# Sheet3.net
KiCad netlist of a schematic drawn in Altium Designer
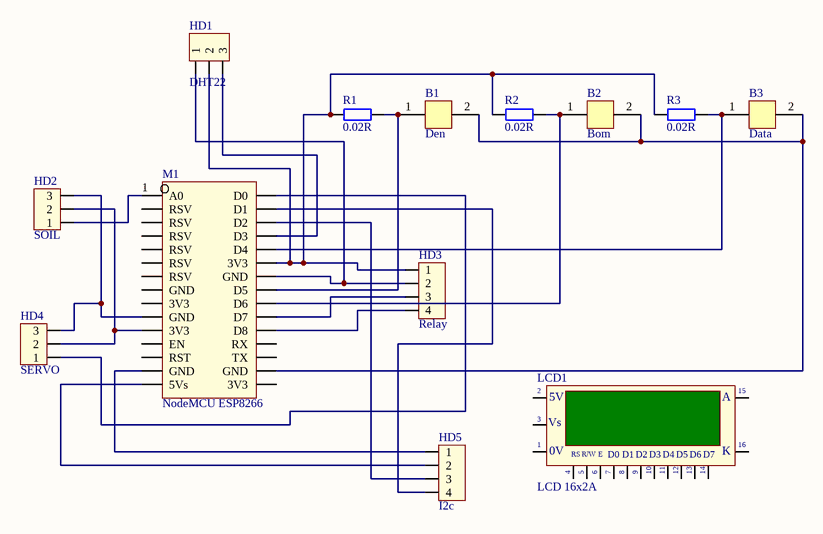
[diagram p0: Sheet3.SchDoc]

(export (version "E")
  (design (tool "Eeschema 10.0.6"))
  (components
    (comp (ref "B1")
      (value "Den")
      (footprint "Button 2 Pin")
      (description "Cắm")
      (libsource (lib "THU VIEN SCH") (part "Nut Nhan 2 Chan  6x6x5MM"))
    )
    (comp (ref "B2")
      (value "Bom")
      (footprint "Button 2 Pin")
      (description "Cắm")
      (libsource (lib "THU VIEN SCH") (part "Nut Nhan 2 Chan  6x6x5MM"))
    )
    (comp (ref "B3")
      (value "Data")
      (footprint "Button 2 Pin")
      (description "Cắm")
      (libsource (lib "THU VIEN SCH") (part "Nut Nhan 2 Chan  6x6x5MM"))
    )
    (comp (ref "HD1")
      (value "DHT22")
      (footprint "HED3")
      (description "Header 3 (Green)")
      (libsource (lib "") (part "Hed3_1"))
    )
    (comp (ref "HD2")
      (value "SOIL")
      (footprint "HED3")
      (description "Header 3 (Green)")
      (libsource (lib "syhaunguyen") (part "Hed3"))
    )
    (comp (ref "HD3")
      (value "Relay")
      (footprint "HED4")
      (description "Header 4 (Green)")
      (libsource (lib "syhaunguyen") (part "Hed4"))
    )
    (comp (ref "HD4")
      (value "SERVO")
      (footprint "HED3")
      (description "Header 3 (Green)")
      (libsource (lib "syhaunguyen") (part "Hed3"))
    )
    (comp (ref "HD5")
      (value "I2c")
      (footprint "HED4")
      (description "Header 4 (Green)")
      (libsource (lib "syhaunguyen") (part "Hed4"))
    )
    (comp (ref "LCD1")
      (value "LCD 16x2A")
      (footprint "LCD16X2")
      (description "LCD dipslay 16 char, 2 line")
      (libsource (lib "My Library") (part "LCD16x2A"))
    )
    (comp (ref "M1")
      (value "NodeMCU ESP8266")
      (footprint "NodeMCU ESP8266")
      (libsource (lib "NodeMCU ESP8266") (part "NodeMCU ESP8266"))
    )
    (comp (ref "R1")
      (value "0.02R")
      (footprint "tro vach 3w")
      (description "Cắm")
      (libsource (lib "THU VIEN SCH") (part "Tro Vach 3W 5% 0.02R"))
    )
    (comp (ref "R2")
      (value "0.02R")
      (footprint "tro vach 3w")
      (description "Cắm")
      (libsource (lib "THU VIEN SCH") (part "Tro Vach 3W 5% 0.02R"))
    )
    (comp (ref "R3")
      (value "0.02R")
      (footprint "tro vach 3w")
      (description "Cắm")
      (libsource (lib "THU VIEN SCH") (part "Tro Vach 3W 5% 0.02R"))
    )
  )
  (nets
    (net (code "1") (name "Net-(B1-Pad2)") (class "Default")
      (node (ref "B1") (pin "2") (pinfunction "2_2") (pintype "passive"))
      (node (ref "B2") (pin "2") (pinfunction "2_2") (pintype "passive"))
      (node (ref "B3") (pin "2") (pinfunction "2_2") (pintype "passive"))
      (node (ref "M1") (pin "17") (pinfunction "GND_17") (pintype "passive"))
    )
    (net (code "2") (name "Net-(HD1-Pad1)") (class "Default")
      (node (ref "HD1") (pin "1") (pinfunction "1_1") (pintype "passive"))
      (node (ref "HD3") (pin "2") (pinfunction "2_2") (pintype "passive"))
      (node (ref "M1") (pin "24") (pinfunction "GND_24") (pintype "passive"))
    )
    (net (code "3") (name "Net-(HD1-Pad2)") (class "Default")
      (node (ref "HD1") (pin "2") (pinfunction "2_2") (pintype "passive"))
      (node (ref "HD3") (pin "1") (pinfunction "1_1") (pintype "passive"))
      (node (ref "M1") (pin "25") (pinfunction "3V3_25") (pintype "passive"))
      (node (ref "R1") (pin "1") (pinfunction "1_1") (pintype "passive"))
      (node (ref "R2") (pin "1") (pinfunction "1_1") (pintype "passive"))
      (node (ref "R3") (pin "1") (pinfunction "1_1") (pintype "passive"))
    )
    (net (code "4") (name "Net-(HD2-Pad2)") (class "Default")
      (node (ref "HD2") (pin "2") (pinfunction "2_2") (pintype "passive"))
      (node (ref "HD4") (pin "2") (pinfunction "2_2") (pintype "passive"))
      (node (ref "M1") (pin "11") (pinfunction "3V3_11") (pintype "passive"))
    )
    (net (code "5") (name "Net-(HD2-Pad3)") (class "Default")
      (node (ref "HD2") (pin "3") (pinfunction "3_3") (pintype "passive"))
      (node (ref "HD4") (pin "3") (pinfunction "3_3") (pintype "passive"))
      (node (ref "M1") (pin "10") (pinfunction "GND_10") (pintype "passive"))
    )
    (net (code "6") (name "Net-(HD5-Pad1)") (class "Default")
      (node (ref "HD5") (pin "1") (pinfunction "1_1") (pintype "passive"))
      (node (ref "M1") (pin "14") (pinfunction "GND_14") (pintype "passive"))
    )
    (net (code "7") (name "Net-(M1-5Vs)") (class "Default")
      (node (ref "HD5") (pin "2") (pinfunction "2_2") (pintype "passive"))
      (node (ref "M1") (pin "15") (pinfunction "5Vs_15") (pintype "passive"))
    )
    (net (code "8") (name "Net-(M1-A0)") (class "Default")
      (node (ref "HD2") (pin "1") (pinfunction "1_1") (pintype "passive"))
      (node (ref "M1") (pin "1") (pinfunction "A0_1") (pintype "passive"))
    )
    (net (code "9") (name "Net-(M1-D0)") (class "Default")
      (node (ref "HD4") (pin "1") (pinfunction "1_1") (pintype "passive"))
      (node (ref "M1") (pin "30") (pinfunction "D0_30") (pintype "passive"))
    )
    (net (code "10") (name "Net-(M1-D1)") (class "Default")
      (node (ref "HD5") (pin "4") (pinfunction "4_4") (pintype "passive"))
      (node (ref "M1") (pin "29") (pinfunction "D1_29") (pintype "passive"))
    )
    (net (code "11") (name "Net-(M1-D2)") (class "Default")
      (node (ref "HD5") (pin "3") (pinfunction "3_3") (pintype "passive"))
      (node (ref "M1") (pin "28") (pinfunction "D2_28") (pintype "passive"))
    )
    (net (code "12") (name "Net-(M1-D3)") (class "Default")
      (node (ref "HD1") (pin "3") (pinfunction "3_3") (pintype "passive"))
      (node (ref "M1") (pin "27") (pinfunction "D3_27") (pintype "passive"))
    )
    (net (code "13") (name "Net-(M1-D4)") (class "Default")
      (node (ref "B3") (pin "1") (pinfunction "1_1") (pintype "passive"))
      (node (ref "M1") (pin "26") (pinfunction "D4_26") (pintype "passive"))
      (node (ref "R3") (pin "2") (pinfunction "2_2") (pintype "passive"))
    )
    (net (code "14") (name "Net-(M1-D5)") (class "Default")
      (node (ref "B1") (pin "1") (pinfunction "1_1") (pintype "passive"))
      (node (ref "M1") (pin "23") (pinfunction "D5_23") (pintype "passive"))
      (node (ref "R1") (pin "2") (pinfunction "2_2") (pintype "passive"))
    )
    (net (code "15") (name "Net-(M1-D6)") (class "Default")
      (node (ref "B2") (pin "1") (pinfunction "1_1") (pintype "passive"))
      (node (ref "M1") (pin "22") (pinfunction "D6_22") (pintype "passive"))
      (node (ref "R2") (pin "2") (pinfunction "2_2") (pintype "passive"))
    )
    (net (code "16") (name "Net-(M1-D7)") (class "Default")
      (node (ref "HD3") (pin "3") (pinfunction "3_3") (pintype "passive"))
      (node (ref "M1") (pin "21") (pinfunction "D7_21") (pintype "passive"))
    )
    (net (code "17") (name "Net-(M1-D8)") (class "Default")
      (node (ref "HD3") (pin "4") (pinfunction "4_4") (pintype "passive"))
      (node (ref "M1") (pin "20") (pinfunction "D8_20") (pintype "passive"))
    )
    (net (code "18") (name "unconnected-(LCD1-A-Pad15)") (class "Default")
      (node (ref "LCD1") (pin "15") (pinfunction "A_15") (pintype "passive"))
    )
    (net (code "19") (name "unconnected-(LCD1-D0-Pad7)") (class "Default")
      (node (ref "LCD1") (pin "7") (pinfunction "D0_7") (pintype "passive"))
    )
    (net (code "20") (name "unconnected-(LCD1-D1-Pad8)") (class "Default")
      (node (ref "LCD1") (pin "8") (pinfunction "D1_8") (pintype "passive"))
    )
    (net (code "21") (name "unconnected-(LCD1-D2-Pad9)") (class "Default")
      (node (ref "LCD1") (pin "9") (pinfunction "D2_9") (pintype "passive"))
    )
    (net (code "22") (name "unconnected-(LCD1-D3-Pad10)") (class "Default")
      (node (ref "LCD1") (pin "10") (pinfunction "D3_10") (pintype "passive"))
    )
    (net (code "23") (name "unconnected-(LCD1-D4-Pad11)") (class "Default")
      (node (ref "LCD1") (pin "11") (pinfunction "D4_11") (pintype "passive"))
    )
    (net (code "24") (name "unconnected-(LCD1-D5-Pad12)") (class "Default")
      (node (ref "LCD1") (pin "12") (pinfunction "D5_12") (pintype "passive"))
    )
    (net (code "25") (name "unconnected-(LCD1-D6-Pad13)") (class "Default")
      (node (ref "LCD1") (pin "13") (pinfunction "D6_13") (pintype "passive"))
    )
    (net (code "26") (name "unconnected-(LCD1-D7-Pad14)") (class "Default")
      (node (ref "LCD1") (pin "14") (pinfunction "D7_14") (pintype "passive"))
    )
    (net (code "27") (name "unconnected-(LCD1-GND-Pad1)") (class "Default")
      (node (ref "LCD1") (pin "1") (pinfunction "GND_1") (pintype "passive"))
    )
    (net (code "28") (name "unconnected-(LCD1-K-Pad16)") (class "Default")
      (node (ref "LCD1") (pin "16") (pinfunction "K_16") (pintype "passive"))
    )
    (net (code "29") (name "unconnected-(LCD1-RS-Pad4)") (class "Default")
      (node (ref "LCD1") (pin "4") (pinfunction "RS_4") (pintype "passive"))
    )
    (net (code "30") (name "unconnected-(LCD1-R{slash}~{W}-Pad5)") (class "Default")
      (node (ref "LCD1") (pin "5") (pinfunction "R/~{W}_5") (pintype "passive"))
    )
    (net (code "31") (name "unconnected-(LCD1-VDD-Pad2)") (class "Default")
      (node (ref "LCD1") (pin "2") (pinfunction "VDD_2") (pintype "passive"))
    )
    (net (code "32") (name "unconnected-(LCD1-VEE-Pad3)") (class "Default")
      (node (ref "LCD1") (pin "3") (pinfunction "VEE_3") (pintype "passive"))
    )
    (net (code "33") (name "unconnected-(LCD1-~{EN}-Pad6)") (class "Default")
      (node (ref "LCD1") (pin "6") (pinfunction "~{EN}_6") (pintype "passive"))
    )
    (net (code "34") (name "unconnected-(M1-3V3-Pad9)") (class "Default")
      (node (ref "M1") (pin "9") (pinfunction "3V3_9") (pintype "passive"))
    )
    (net (code "35") (name "unconnected-(M1-3V3-Pad16)") (class "Default")
      (node (ref "M1") (pin "16") (pinfunction "3V3_16") (pintype "passive"))
    )
    (net (code "36") (name "unconnected-(M1-EN-Pad12)") (class "Default")
      (node (ref "M1") (pin "12") (pinfunction "EN_12") (pintype "passive"))
    )
    (net (code "37") (name "unconnected-(M1-GND-Pad8)") (class "Default")
      (node (ref "M1") (pin "8") (pinfunction "GND_8") (pintype "passive"))
    )
    (net (code "38") (name "unconnected-(M1-RST-Pad13)") (class "Default")
      (node (ref "M1") (pin "13") (pinfunction "RST_13") (pintype "passive"))
    )
    (net (code "39") (name "unconnected-(M1-RSV-Pad2)") (class "Default")
      (node (ref "M1") (pin "2") (pinfunction "RSV_2") (pintype "passive"))
    )
    (net (code "40") (name "unconnected-(M1-RSV-Pad3)") (class "Default")
      (node (ref "M1") (pin "3") (pinfunction "RSV_3") (pintype "passive"))
    )
    (net (code "41") (name "unconnected-(M1-RSV-Pad4)") (class "Default")
      (node (ref "M1") (pin "4") (pinfunction "RSV_4") (pintype "passive"))
    )
    (net (code "42") (name "unconnected-(M1-RSV-Pad5)") (class "Default")
      (node (ref "M1") (pin "5") (pinfunction "RSV_5") (pintype "passive"))
    )
    (net (code "43") (name "unconnected-(M1-RSV-Pad6)") (class "Default")
      (node (ref "M1") (pin "6") (pinfunction "RSV_6") (pintype "passive"))
    )
    (net (code "44") (name "unconnected-(M1-RSV-Pad7)") (class "Default")
      (node (ref "M1") (pin "7") (pinfunction "RSV_7") (pintype "passive"))
    )
    (net (code "45") (name "unconnected-(M1-RX-Pad19)") (class "Default")
      (node (ref "M1") (pin "19") (pinfunction "RX_19") (pintype "passive"))
    )
    (net (code "46") (name "unconnected-(M1-TX-Pad18)") (class "Default")
      (node (ref "M1") (pin "18") (pinfunction "TX_18") (pintype "passive"))
    )
  )
)
